# MCU.net
KiCad netlist of a schematic drawn in Altium Designer
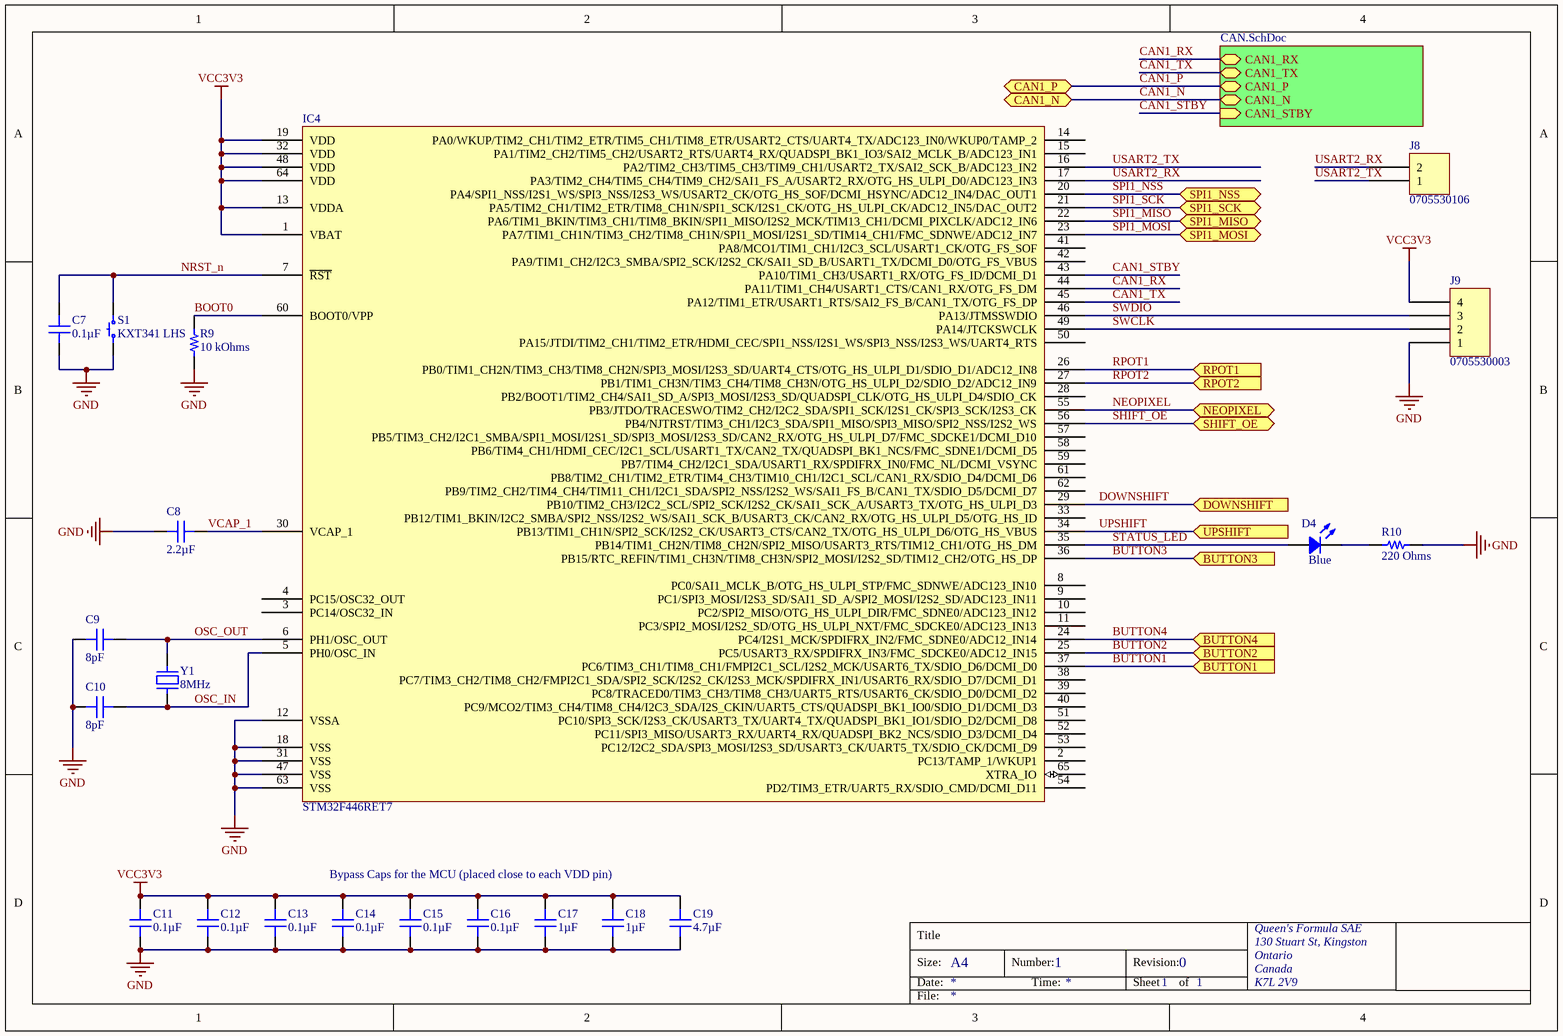
[diagram p0: MCU.SchDoc]

(export (version "E")
  (design (tool "Eeschema 10.0.6"))
  (components
    (comp (ref "C7")
      (value "0.1µF")
      (footprint "CAP 0402_1005")
      (description "CAP CER 0402 0.1UF 16V X7R 10%")
      (fields (field (name "PART NUMBER") "C0402C104K4RECAUTO") (field (name "MANUFACTURER") "KEMET"))
      (libsource (lib "CAL") (part "Capacitor"))
    )
    (comp (ref "C8")
      (value "2.2µF")
      (footprint "CAP 0402_1005")
      (description "CAP CER 2.2UF 16V X5R 0402")
      (fields
        (field (name "PART NUMBER") "CL05A225KO5NQNC")
        (field (name "MANUFACTURER") "Samsung Electro-Mechanics")
      )
      (libsource (lib "CAL") (part "Capacitor"))
    )
    (comp (ref "C9")
      (value "8pF")
      (footprint "CAP 0402_1005")
      (description "CAP CER 8PF 50V NP0 0402")
      (fields
        (field (name "PART NUMBER") "C1005NP01H080D050BA")
        (field (name "MANUFACTURER") "TDK Corporation")
      )
      (libsource (lib "Celestial") (part "Capacitor"))
    )
    (comp (ref "C10")
      (value "8pF")
      (footprint "CAP 0402_1005")
      (description "CAP CER 8PF 50V NP0 0402")
      (fields
        (field (name "PART NUMBER") "C1005NP01H080D050BA")
        (field (name "MANUFACTURER") "TDK Corporation")
      )
      (libsource (lib "Celestial") (part "Capacitor"))
    )
    (comp (ref "C11")
      (value "0.1µF")
      (footprint "CAP 0402_1005")
      (description "CAP CER 0402 0.1UF 16V X7R 10%")
      (fields (field (name "PART NUMBER") "C0402C104K4RECAUTO") (field (name "MANUFACTURER") "KEMET"))
      (libsource (lib "CAL") (part "Capacitor"))
    )
    (comp (ref "C12")
      (value "0.1µF")
      (footprint "CAP 0402_1005")
      (description "CAP CER 0402 0.1UF 16V X7R 10%")
      (fields (field (name "PART NUMBER") "C0402C104K4RECAUTO") (field (name "MANUFACTURER") "KEMET"))
      (libsource (lib "CAL") (part "Capacitor"))
    )
    (comp (ref "C13")
      (value "0.1µF")
      (footprint "CAP 0402_1005")
      (description "CAP CER 0402 0.1UF 16V X7R 10%")
      (fields (field (name "PART NUMBER") "C0402C104K4RECAUTO") (field (name "MANUFACTURER") "KEMET"))
      (libsource (lib "CAL") (part "Capacitor"))
    )
    (comp (ref "C14")
      (value "0.1µF")
      (footprint "CAP 0402_1005")
      (description "CAP CER 0402 0.1UF 16V X7R 10%")
      (fields (field (name "PART NUMBER") "C0402C104K4RECAUTO") (field (name "MANUFACTURER") "KEMET"))
      (libsource (lib "CAL") (part "Capacitor"))
    )
    (comp (ref "C15")
      (value "0.1µF")
      (footprint "CAP 0402_1005")
      (description "CAP CER 0402 0.1UF 16V X7R 10%")
      (fields (field (name "PART NUMBER") "C0402C104K4RECAUTO") (field (name "MANUFACTURER") "KEMET"))
      (libsource (lib "CAL") (part "Capacitor"))
    )
    (comp (ref "C16")
      (value "0.1µF")
      (footprint "CAP 0402_1005")
      (description "CAP CER 0402 0.1UF 16V X7R 10%")
      (fields (field (name "PART NUMBER") "C0402C104K4RECAUTO") (field (name "MANUFACTURER") "KEMET"))
      (libsource (lib "CAL") (part "Capacitor"))
    )
    (comp (ref "C17")
      (value "1µF")
      (footprint "CAP 0402_1005")
      (description "CAP CER 1UF 10V X5R 0402")
      (fields
        (field (name "PART NUMBER") "CGB2A1X5R1A105K033BC")
        (field (name "MANUFACTURER") "TDK Corporation")
      )
      (libsource (lib "CAL") (part "Capacitor"))
    )
    (comp (ref "C18")
      (value "1µF")
      (footprint "CAP 0402_1005")
      (description "CAP CER 1UF 10V X5R 0402")
      (fields
        (field (name "PART NUMBER") "CGB2A1X5R1A105K033BC")
        (field (name "MANUFACTURER") "TDK Corporation")
      )
      (libsource (lib "CAL") (part "Capacitor"))
    )
    (comp (ref "C19")
      (value "4.7µF")
      (footprint "CAP 0402_1005")
      (description "CAP CER 4.7UF 10V X5R 0402")
      (fields
        (field (name "PART NUMBER") "C1005X5R1A475K050BC")
        (field (name "MANUFACTURER") "TDK Corporation")
      )
      (libsource (lib "CAL") (part "Capacitor"))
    )
    (comp (ref "D4")
      (value "Blue")
      (footprint "LED 0402_1005 BLUE")
      (description "LED BLUE CLEAR CHIP SMD")
      (fields (field (name "PART NUMBER") "APHHS1005QBC/D") (field (name "MANUFACTURER") "Kingbright"))
      (libsource (lib "Celestial") (part "LED"))
    )
    (comp (ref "IC4")
      (value "STM32F446RET7")
      (footprint "ST LQFP-64 10X10MM")
      (description "IC MCU 32BIT 512KB FLASH 64LQFP")
      (fields (field (name "MANUFACTURER") "STMicroelectronics"))
      (libsource (lib "Celestial") (part "ST STM32F446 64PIN"))
    )
    (comp (ref "J8")
      (value "0705530106")
      (footprint "MOLEX SDA-70553-2PIN")
      (description "CONN HEADER R/A 2POS 2.54MM")
      (fields (field (name "MANUFACTURER") "Molex"))
      (libsource (lib "Celestial") (part "2 Pin"))
    )
    (comp (ref "J9")
      (value "0705530003")
      (footprint "MOLEX SDA-70553-4PIN")
      (description "CONN HEADER R/A 4POS 2.54MM")
      (fields (field (name "MANUFACTURER") "Molex"))
      (libsource (lib "Celestial") (part "4 Pin"))
    )
    (comp (ref "R9")
      (value "10 kOhms")
      (footprint "RES 0402_1005")
      (description "RES SMD 10K OHM 0.5% 1/16W 0402")
      (fields (field (name "PART NUMBER") "CRCW040210K0DHEDP") (field (name "MANUFACTURER") "Vishay Dale"))
      (libsource (lib "CAL") (part "Resistor"))
    )
    (comp (ref "R10")
      (value "220 Ohms")
      (footprint "RES 0402_1005")
      (description "CRGCQ 0402 220R 5%")
      (fields
        (field (name "PART NUMBER") "CRGCQ0402J220R")
        (field (name "MANUFACTURER") "TE Connectivity Passive Product")
      )
      (libsource (lib "CAL") (part "Resistor"))
    )
    (comp (ref "S1")
      (value "KXT341 LHS")
      (footprint "C&K KXT3")
      (description "SWITCH TACTILE SPST-NO 0.02A 15V")
      (fields (field (name "MANUFACTURER") "C&K"))
      (libsource (lib "Celestial") (part "SPST-NO 2 PIN"))
    )
    (comp (ref "Y1")
      (value "8MHz")
      (footprint "NDK NX3225GD")
      (description "CRYSTAL 8.0000MHZ 8PF SMD")
      (fields
        (field (name "PART NUMBER") "NX3225GD-8MHZ-STD-CRA-3")
        (field (name "MANUFACTURER") "NDK America, Inc.")
      )
      (libsource (lib "Celestial") (part "NDK NX3225GD"))
    )
  )
  (nets
    (net (code "1") (name "/BOOT0") (class "Default")
      (node (ref "IC4") (pin "60") (pinfunction "BOOT0/VPP_60") (pintype "passive"))
      (node (ref "R9") (pin "2") (pinfunction "2_2") (pintype "passive"))
    )
    (net (code "2") (name "/BUTTON1") (class "Default")
      (node (ref "IC4") (pin "37") (pinfunction "PC6/TIM3_CH1/TIM8_CH1/FMPI2C1_SCL/I2S2_MCK/USART6_TX/SDIO_D6/DCMI_D0_37") (pintype "passive"))
    )
    (net (code "3") (name "/BUTTON2") (class "Default")
      (node (ref "IC4") (pin "25") (pinfunction "PC5/USART3_RX/SPDIFRX_IN3/FMC_SDCKE0/ADC12_IN15_25") (pintype "passive"))
    )
    (net (code "4") (name "/BUTTON3") (class "Default")
      (node (ref "IC4") (pin "36") (pinfunction "PB15/RTC_REFIN/TIM1_CH3N/TIM8_CH3N/SPI2_MOSI/I2S2_SD/TIM12_CH2/OTG_HS_DP_36") (pintype "passive"))
    )
    (net (code "5") (name "/BUTTON4") (class "Default")
      (node (ref "IC4") (pin "24") (pinfunction "PC4/I2S1_MCK/SPDIFRX_IN2/FMC_SDNE0/ADC12_IN14_24") (pintype "passive"))
    )
    (net (code "8") (name "/CAN1_RX") (class "Default")
      (node (ref "IC4") (pin "44") (pinfunction "PA11/TIM1_CH4/USART1_CTS/CAN1_RX/OTG_FS_DM_44") (pintype "passive"))
    )
    (net (code "9") (name "/CAN1_STBY") (class "Default")
      (node (ref "IC4") (pin "43") (pinfunction "PA10/TIM1_CH3/USART1_RX/OTG_FS_ID/DCMI_D1_43") (pintype "passive"))
    )
    (net (code "10") (name "/CAN1_TX") (class "Default")
      (node (ref "IC4") (pin "45") (pinfunction "PA12/TIM1_ETR/USART1_RTS/SAI2_FS_B/CAN1_TX/OTG_FS_DP_45") (pintype "passive"))
    )
    (net (code "11") (name "/DOWNSHIFT") (class "Default")
      (node (ref "IC4") (pin "29") (pinfunction "PB10/TIM2_CH3/I2C2_SCL/SPI2_SCK/I2S2_CK/SAI1_SCK_A/USART3_TX/OTG_HS_ULPI_D3_29") (pintype "passive"))
    )
    (net (code "12") (name "/NEOPIXEL") (class "Default")
      (node (ref "IC4") (pin "55") (pinfunction "PB3/JTDO/TRACESWO/TIM2_CH2/I2C2_SDA/SPI1_SCK/I2S1_CK/SPI3_SCK/I2S3_CK_55") (pintype "passive"))
    )
    (net (code "13") (name "/NRST_n") (class "Default")
      (node (ref "C7") (pin "2") (pinfunction "2_2") (pintype "passive"))
      (node (ref "IC4") (pin "7") (pinfunction "~{RST}_7") (pintype "passive"))
      (node (ref "S1") (pin "2") (pinfunction "2_2") (pintype "passive"))
    )
    (net (code "14") (name "/OSC_IN") (class "Default")
      (node (ref "C10") (pin "2") (pinfunction "2_2") (pintype "passive"))
      (node (ref "IC4") (pin "5") (pinfunction "PH0/OSC_IN_5") (pintype "passive"))
      (node (ref "Y1") (pin "1") (pinfunction "1_1") (pintype "passive"))
    )
    (net (code "15") (name "/OSC_OUT") (class "Default")
      (node (ref "C9") (pin "2") (pinfunction "2_2") (pintype "passive"))
      (node (ref "IC4") (pin "6") (pinfunction "PH1/OSC_OUT_6") (pintype "passive"))
      (node (ref "Y1") (pin "2") (pinfunction "2_2") (pintype "passive"))
    )
    (net (code "16") (name "/RPOT1") (class "Default")
      (node (ref "IC4") (pin "26") (pinfunction "PB0/TIM1_CH2N/TIM3_CH3/TIM8_CH2N/SPI3_MOSI/I2S3_SD/UART4_CTS/OTG_HS_ULPI_D1/SDIO_D1/ADC12_IN8_26") (pintype "passive"))
    )
    (net (code "17") (name "/RPOT2") (class "Default")
      (node (ref "IC4") (pin "27") (pinfunction "PB1/TIM1_CH3N/TIM3_CH4/TIM8_CH3N/OTG_HS_ULPI_D2/SDIO_D2/ADC12_IN9_27") (pintype "passive"))
    )
    (net (code "18") (name "/SHIFT_OE") (class "Default")
      (node (ref "IC4") (pin "56") (pinfunction "PB4/NJTRST/TIM3_CH1/I2C3_SDA/SPI1_MISO/SPI3_MISO/SPI2_NSS/I2S2_WS_56") (pintype "passive"))
    )
    (net (code "19") (name "/SPI1_MISO") (class "Default")
      (node (ref "IC4") (pin "22") (pinfunction "PA6/TIM1_BKIN/TIM3_CH1/TIM8_BKIN/SPI1_MISO/I2S2_MCK/TIM13_CH1/DCMI_PIXCLK/ADC12_IN6_22") (pintype "passive"))
    )
    (net (code "20") (name "/SPI1_MOSI") (class "Default")
      (node (ref "IC4") (pin "23") (pinfunction "PA7/TIM1_CH1N/TIM3_CH2/TIM8_CH1N/SPI1_MOSI/I2S1_SD/TIM14_CH1/FMC_SDNWE/ADC12_IN7_23") (pintype "passive"))
    )
    (net (code "21") (name "/SPI1_NSS") (class "Default")
      (node (ref "IC4") (pin "20") (pinfunction "PA4/SPI1_NSS/I2S1_WS/SPI3_NSS/I2S3_WS/USART2_CK/OTG_HS_SOF/DCMI_HSYNC/ADC12_IN4/DAC_OUT1_20") (pintype "passive"))
    )
    (net (code "22") (name "/SPI1_SCK") (class "Default")
      (node (ref "IC4") (pin "21") (pinfunction "PA5/TIM2_CH1/TIM2_ETR/TIM8_CH1N/SPI1_SCK/I2S1_CK/OTG_HS_ULPI_CK/ADC12_IN5/DAC_OUT2_21") (pintype "passive"))
    )
    (net (code "23") (name "/STATUS_LED") (class "Default")
      (node (ref "D4") (pin "1") (pinfunction "1_1") (pintype "passive"))
      (node (ref "IC4") (pin "35") (pinfunction "PB14/TIM1_CH2N/TIM8_CH2N/SPI2_MISO/USART3_RTS/TIM12_CH1/OTG_HS_DM_35") (pintype "passive"))
    )
    (net (code "24") (name "/SWCLK") (class "Default")
      (node (ref "IC4") (pin "49") (pinfunction "PA14/JTCKSWCLK_49") (pintype "passive"))
      (node (ref "J9") (pin "2") (pinfunction "2_2") (pintype "passive"))
    )
    (net (code "25") (name "/SWDIO") (class "Default")
      (node (ref "IC4") (pin "46") (pinfunction "PA13/JTMSSWDIO_46") (pintype "passive"))
      (node (ref "J9") (pin "3") (pinfunction "3_3") (pintype "passive"))
    )
    (net (code "26") (name "/UPSHIFT") (class "Default")
      (node (ref "IC4") (pin "34") (pinfunction "PB13/TIM1_CH1N/SPI2_SCK/I2S2_CK/USART3_CTS/CAN2_TX/OTG_HS_ULPI_D6/OTG_HS_VBUS_34") (pintype "passive"))
    )
    (net (code "27") (name "/USART2_RX") (class "Default")
      (node (ref "IC4") (pin "17") (pinfunction "PA3/TIM2_CH4/TIM5_CH4/TIM9_CH2/SAI1_FS_A/USART2_RX/OTG_HS_ULPI_D0/ADC123_IN3_17") (pintype "passive"))
      (node (ref "J8") (pin "2") (pinfunction "2_2") (pintype "passive"))
    )
    (net (code "28") (name "/USART2_TX") (class "Default")
      (node (ref "IC4") (pin "16") (pinfunction "PA2/TIM2_CH3/TIM5_CH3/TIM9_CH1/USART2_TX/SAI2_SCK_B/ADC123_IN2_16") (pintype "passive"))
      (node (ref "J8") (pin "1") (pinfunction "1_1") (pintype "passive"))
    )
    (net (code "29") (name "/VCAP_1") (class "Default")
      (node (ref "C8") (pin "1") (pinfunction "1_1") (pintype "passive"))
      (node (ref "IC4") (pin "30") (pinfunction "VCAP_1_30") (pintype "passive"))
    )
    (net (code "30") (name "GND") (class "Default")
      (node (ref "C10") (pin "1") (pinfunction "1_1") (pintype "passive"))
      (node (ref "C11") (pin "1") (pinfunction "1_1") (pintype "passive"))
      (node (ref "C12") (pin "1") (pinfunction "1_1") (pintype "passive"))
      (node (ref "C13") (pin "1") (pinfunction "1_1") (pintype "passive"))
      (node (ref "C14") (pin "1") (pinfunction "1_1") (pintype "passive"))
      (node (ref "C15") (pin "1") (pinfunction "1_1") (pintype "passive"))
      (node (ref "C16") (pin "1") (pinfunction "1_1") (pintype "passive"))
      (node (ref "C17") (pin "1") (pinfunction "1_1") (pintype "passive"))
      (node (ref "C18") (pin "1") (pinfunction "1_1") (pintype "passive"))
      (node (ref "C19") (pin "1") (pinfunction "1_1") (pintype "passive"))
      (node (ref "C7") (pin "1") (pinfunction "1_1") (pintype "passive"))
      (node (ref "C8") (pin "2") (pinfunction "2_2") (pintype "passive"))
      (node (ref "C9") (pin "1") (pinfunction "1_1") (pintype "passive"))
      (node (ref "IC4") (pin "12") (pinfunction "VSSA_12") (pintype "passive"))
      (node (ref "IC4") (pin "18") (pinfunction "VSS_18") (pintype "passive"))
      (node (ref "IC4") (pin "31") (pinfunction "VSS_31") (pintype "passive"))
      (node (ref "IC4") (pin "47") (pinfunction "VSS_47") (pintype "passive"))
      (node (ref "IC4") (pin "63") (pinfunction "VSS_63") (pintype "passive"))
      (node (ref "J9") (pin "1") (pinfunction "1_1") (pintype "passive"))
      (node (ref "R10") (pin "2") (pinfunction "2_2") (pintype "passive"))
      (node (ref "R9") (pin "1") (pinfunction "1_1") (pintype "passive"))
      (node (ref "S1") (pin "1") (pinfunction "1_1") (pintype "passive"))
    )
    (net (code "31") (name "Net-(D4-Pad2)") (class "Default")
      (node (ref "D4") (pin "2") (pinfunction "2_2") (pintype "passive"))
      (node (ref "R10") (pin "1") (pinfunction "1_1") (pintype "passive"))
    )
    (net (code "32") (name "VCC3V3") (class "Default")
      (node (ref "C11") (pin "2") (pinfunction "2_2") (pintype "passive"))
      (node (ref "C12") (pin "2") (pinfunction "2_2") (pintype "passive"))
      (node (ref "C13") (pin "2") (pinfunction "2_2") (pintype "passive"))
      (node (ref "C14") (pin "2") (pinfunction "2_2") (pintype "passive"))
      (node (ref "C15") (pin "2") (pinfunction "2_2") (pintype "passive"))
      (node (ref "C16") (pin "2") (pinfunction "2_2") (pintype "passive"))
      (node (ref "C17") (pin "2") (pinfunction "2_2") (pintype "passive"))
      (node (ref "C18") (pin "2") (pinfunction "2_2") (pintype "passive"))
      (node (ref "C19") (pin "2") (pinfunction "2_2") (pintype "passive"))
      (node (ref "IC4") (pin "1") (pinfunction "VBAT_1") (pintype "passive"))
      (node (ref "IC4") (pin "13") (pinfunction "VDDA_13") (pintype "passive"))
      (node (ref "IC4") (pin "19") (pinfunction "VDD_19") (pintype "passive"))
      (node (ref "IC4") (pin "32") (pinfunction "VDD_32") (pintype "passive"))
      (node (ref "IC4") (pin "48") (pinfunction "VDD_48") (pintype "passive"))
      (node (ref "IC4") (pin "64") (pinfunction "VDD_64") (pintype "passive"))
      (node (ref "J9") (pin "4") (pinfunction "4_4") (pintype "passive"))
    )
    (net (code "33") (name "unconnected-(IC4-PA0{slash}WKUP{slash}TIM2_CH1{slash}TIM2_ETR{slash}TIM5_CH1{slash}TIM8_ETR{slash}USART2_CTS{slash}UART4_TX{slash}ADC123_IN0{slash}WKUP0{slash}TAMP_2-Pad14)") (class "Default")
      (node (ref "IC4") (pin "14") (pinfunction "PA0/WKUP/TIM2_CH1/TIM2_ETR/TIM5_CH1/TIM8_ETR/USART2_CTS/UART4_TX/ADC123_IN0/WKUP0/TAMP_2_14") (pintype "passive"))
    )
    (net (code "34") (name "unconnected-(IC4-PA1{slash}TIM2_CH2{slash}TIM5_CH2{slash}USART2_RTS{slash}UART4_RX{slash}QUADSPI_BK1_IO3{slash}SAI2_MCLK_B{slash}ADC123_IN1-Pad15)") (class "Default")
      (node (ref "IC4") (pin "15") (pinfunction "PA1/TIM2_CH2/TIM5_CH2/USART2_RTS/UART4_RX/QUADSPI_BK1_IO3/SAI2_MCLK_B/ADC123_IN1_15") (pintype "passive"))
    )
    (net (code "35") (name "unconnected-(IC4-PA8{slash}MCO1{slash}TIM1_CH1{slash}I2C3_SCL{slash}USART1_CK{slash}OTG_FS_SOF-Pad41)") (class "Default")
      (node (ref "IC4") (pin "41") (pinfunction "PA8/MCO1/TIM1_CH1/I2C3_SCL/USART1_CK/OTG_FS_SOF_41") (pintype "passive"))
    )
    (net (code "36") (name "unconnected-(IC4-PA9{slash}TIM1_CH2{slash}I2C3_SMBA{slash}SPI2_SCK{slash}I2S2_CK{slash}SAI1_SD_B{slash}USART1_TX{slash}DCMI_D0{slash}OTG_FS_VBUS-Pad42)") (class "Default")
      (node (ref "IC4") (pin "42") (pinfunction "PA9/TIM1_CH2/I2C3_SMBA/SPI2_SCK/I2S2_CK/SAI1_SD_B/USART1_TX/DCMI_D0/OTG_FS_VBUS_42") (pintype "passive"))
    )
    (net (code "37") (name "unconnected-(IC4-PA15{slash}JTDI{slash}TIM2_CH1{slash}TIM2_ETR{slash}HDMI_CEC{slash}SPI1_NSS{slash}I2S1_WS{slash}SPI3_NSS{slash}I2S3_WS{slash}UART4_RTS-Pad50)") (class "Default")
      (node (ref "IC4") (pin "50") (pinfunction "PA15/JTDI/TIM2_CH1/TIM2_ETR/HDMI_CEC/SPI1_NSS/I2S1_WS/SPI3_NSS/I2S3_WS/UART4_RTS_50") (pintype "passive"))
    )
    (net (code "38") (name "unconnected-(IC4-PB2{slash}BOOT1{slash}TIM2_CH4{slash}SAI1_SD_A{slash}SPI3_MOSI{slash}I2S3_SD{slash}QUADSPI_CLK{slash}OTG_HS_ULPI_D4{slash}SDIO_CK-Pad28)") (class "Default")
      (node (ref "IC4") (pin "28") (pinfunction "PB2/BOOT1/TIM2_CH4/SAI1_SD_A/SPI3_MOSI/I2S3_SD/QUADSPI_CLK/OTG_HS_ULPI_D4/SDIO_CK_28") (pintype "passive"))
    )
    (net (code "39") (name "unconnected-(IC4-PB5{slash}TIM3_CH2{slash}I2C1_SMBA{slash}SPI1_MOSI{slash}I2S1_SD{slash}SPI3_MOSI{slash}I2S3_SD{slash}CAN2_RX{slash}OTG_HS_ULPI_D7{slash}FMC_SDCKE1{slash}DCMI_D10-Pad57)") (class "Default")
      (node (ref "IC4") (pin "57") (pinfunction "PB5/TIM3_CH2/I2C1_SMBA/SPI1_MOSI/I2S1_SD/SPI3_MOSI/I2S3_SD/CAN2_RX/OTG_HS_ULPI_D7/FMC_SDCKE1/DCMI_D10_57") (pintype "passive"))
    )
    (net (code "40") (name "unconnected-(IC4-PB6{slash}TIM4_CH1{slash}HDMI_CEC{slash}I2C1_SCL{slash}USART1_TX{slash}CAN2_TX{slash}QUADSPI_BK1_NCS{slash}FMC_SDNE1{slash}DCMI_D5-Pad58)") (class "Default")
      (node (ref "IC4") (pin "58") (pinfunction "PB6/TIM4_CH1/HDMI_CEC/I2C1_SCL/USART1_TX/CAN2_TX/QUADSPI_BK1_NCS/FMC_SDNE1/DCMI_D5_58") (pintype "passive"))
    )
    (net (code "41") (name "unconnected-(IC4-PB7{slash}TIM4_CH2{slash}I2C1_SDA{slash}USART1_RX{slash}SPDIFRX_IN0{slash}FMC_NL{slash}DCMI_VSYNC-Pad59)") (class "Default")
      (node (ref "IC4") (pin "59") (pinfunction "PB7/TIM4_CH2/I2C1_SDA/USART1_RX/SPDIFRX_IN0/FMC_NL/DCMI_VSYNC_59") (pintype "passive"))
    )
    (net (code "42") (name "unconnected-(IC4-PB8{slash}TIM2_CH1{slash}TIM2_ETR{slash}TIM4_CH3{slash}TIM10_CH1{slash}I2C1_SCL{slash}CAN1_RX{slash}SDIO_D4{slash}DCMI_D6-Pad61)") (class "Default")
      (node (ref "IC4") (pin "61") (pinfunction "PB8/TIM2_CH1/TIM2_ETR/TIM4_CH3/TIM10_CH1/I2C1_SCL/CAN1_RX/SDIO_D4/DCMI_D6_61") (pintype "passive"))
    )
    (net (code "43") (name "unconnected-(IC4-PB9{slash}TIM2_CH2{slash}TIM4_CH4{slash}TIM11_CH1{slash}I2C1_SDA{slash}SPI2_NSS{slash}I2S2_WS{slash}SAI1_FS_B{slash}CAN1_TX{slash}SDIO_D5{slash}DCMI_D7-Pad62)") (class "Default")
      (node (ref "IC4") (pin "62") (pinfunction "PB9/TIM2_CH2/TIM4_CH4/TIM11_CH1/I2C1_SDA/SPI2_NSS/I2S2_WS/SAI1_FS_B/CAN1_TX/SDIO_D5/DCMI_D7_62") (pintype "passive"))
    )
    (net (code "44") (name "unconnected-(IC4-PB12{slash}TIM1_BKIN{slash}I2C2_SMBA{slash}SPI2_NSS{slash}I2S2_WS{slash}SAI1_SCK_B{slash}USART3_CK{slash}CAN2_RX{slash}OTG_HS_ULPI_D5{slash}OTG_HS_ID-Pad33)") (class "Default")
      (node (ref "IC4") (pin "33") (pinfunction "PB12/TIM1_BKIN/I2C2_SMBA/SPI2_NSS/I2S2_WS/SAI1_SCK_B/USART3_CK/CAN2_RX/OTG_HS_ULPI_D5/OTG_HS_ID_33") (pintype "passive"))
    )
    (net (code "45") (name "unconnected-(IC4-PC0{slash}SAI1_MCLK_B{slash}OTG_HS_ULPI_STP{slash}FMC_SDNWE{slash}ADC123_IN10-Pad8)") (class "Default")
      (node (ref "IC4") (pin "8") (pinfunction "PC0/SAI1_MCLK_B/OTG_HS_ULPI_STP/FMC_SDNWE/ADC123_IN10_8") (pintype "passive"))
    )
    (net (code "46") (name "unconnected-(IC4-PC1{slash}SPI3_MOSI{slash}I2S3_SD{slash}SAI1_SD_A{slash}SPI2_MOSI{slash}I2S2_SD{slash}ADC123_IN11-Pad9)") (class "Default")
      (node (ref "IC4") (pin "9") (pinfunction "PC1/SPI3_MOSI/I2S3_SD/SAI1_SD_A/SPI2_MOSI/I2S2_SD/ADC123_IN11_9") (pintype "passive"))
    )
    (net (code "47") (name "unconnected-(IC4-PC2{slash}SPI2_MISO{slash}OTG_HS_ULPI_DIR{slash}FMC_SDNE0{slash}ADC123_IN12-Pad10)") (class "Default")
      (node (ref "IC4") (pin "10") (pinfunction "PC2/SPI2_MISO/OTG_HS_ULPI_DIR/FMC_SDNE0/ADC123_IN12_10") (pintype "passive"))
    )
    (net (code "48") (name "unconnected-(IC4-PC3{slash}SPI2_MOSI{slash}I2S2_SD{slash}OTG_HS_ULPI_NXT{slash}FMC_SDCKE0{slash}ADC123_IN13-Pad11)") (class "Default")
      (node (ref "IC4") (pin "11") (pinfunction "PC3/SPI2_MOSI/I2S2_SD/OTG_HS_ULPI_NXT/FMC_SDCKE0/ADC123_IN13_11") (pintype "passive"))
    )
    (net (code "49") (name "unconnected-(IC4-PC7{slash}TIM3_CH2{slash}TIM8_CH2{slash}FMPI2C1_SDA{slash}SPI2_SCK{slash}I2S2_CK{slash}I2S3_MCK{slash}SPDIFRX_IN1{slash}USART6_RX{slash}SDIO_D7{slash}DCMI_D1-Pad38)") (class "Default")
      (node (ref "IC4") (pin "38") (pinfunction "PC7/TIM3_CH2/TIM8_CH2/FMPI2C1_SDA/SPI2_SCK/I2S2_CK/I2S3_MCK/SPDIFRX_IN1/USART6_RX/SDIO_D7/DCMI_D1_38") (pintype "passive"))
    )
    (net (code "50") (name "unconnected-(IC4-PC8{slash}TRACED0{slash}TIM3_CH3{slash}TIM8_CH3{slash}UART5_RTS{slash}USART6_CK{slash}SDIO_D0{slash}DCMI_D2-Pad39)") (class "Default")
      (node (ref "IC4") (pin "39") (pinfunction "PC8/TRACED0/TIM3_CH3/TIM8_CH3/UART5_RTS/USART6_CK/SDIO_D0/DCMI_D2_39") (pintype "passive"))
    )
    (net (code "51") (name "unconnected-(IC4-PC9{slash}MCO2{slash}TIM3_CH4{slash}TIM8_CH4{slash}I2C3_SDA{slash}I2S_CKIN{slash}UART5_CTS{slash}QUADSPI_BK1_IO0{slash}SDIO_D1{slash}DCMI_D3-Pad40)") (class "Default")
      (node (ref "IC4") (pin "40") (pinfunction "PC9/MCO2/TIM3_CH4/TIM8_CH4/I2C3_SDA/I2S_CKIN/UART5_CTS/QUADSPI_BK1_IO0/SDIO_D1/DCMI_D3_40") (pintype "passive"))
    )
    (net (code "52") (name "unconnected-(IC4-PC10{slash}SPI3_SCK{slash}I2S3_CK{slash}USART3_TX{slash}UART4_TX{slash}QUADSPI_BK1_IO1{slash}SDIO_D2{slash}DCMI_D8-Pad51)") (class "Default")
      (node (ref "IC4") (pin "51") (pinfunction "PC10/SPI3_SCK/I2S3_CK/USART3_TX/UART4_TX/QUADSPI_BK1_IO1/SDIO_D2/DCMI_D8_51") (pintype "passive"))
    )
    (net (code "53") (name "unconnected-(IC4-PC11{slash}SPI3_MISO{slash}USART3_RX{slash}UART4_RX{slash}QUADSPI_BK2_NCS{slash}SDIO_D3{slash}DCMI_D4-Pad52)") (class "Default")
      (node (ref "IC4") (pin "52") (pinfunction "PC11/SPI3_MISO/USART3_RX/UART4_RX/QUADSPI_BK2_NCS/SDIO_D3/DCMI_D4_52") (pintype "passive"))
    )
    (net (code "54") (name "unconnected-(IC4-PC12{slash}I2C2_SDA{slash}SPI3_MOSI{slash}I2S3_SD{slash}USART3_CK{slash}UART5_TX{slash}SDIO_CK{slash}DCMI_D9-Pad53)") (class "Default")
      (node (ref "IC4") (pin "53") (pinfunction "PC12/I2C2_SDA/SPI3_MOSI/I2S3_SD/USART3_CK/UART5_TX/SDIO_CK/DCMI_D9_53") (pintype "passive"))
    )
    (net (code "55") (name "unconnected-(IC4-PC13{slash}TAMP_1{slash}WKUP1-Pad2)") (class "Default")
      (node (ref "IC4") (pin "2") (pinfunction "PC13/TAMP_1/WKUP1_2") (pintype "passive"))
    )
    (net (code "56") (name "unconnected-(IC4-PC14{slash}OSC32_IN-Pad3)") (class "Default")
      (node (ref "IC4") (pin "3") (pinfunction "PC14/OSC32_IN_3") (pintype "passive"))
    )
    (net (code "57") (name "unconnected-(IC4-PC15{slash}OSC32_OUT-Pad4)") (class "Default")
      (node (ref "IC4") (pin "4") (pinfunction "PC15/OSC32_OUT_4") (pintype "passive"))
    )
    (net (code "58") (name "unconnected-(IC4-PD2{slash}TIM3_ETR{slash}UART5_RX{slash}SDIO_CMD{slash}DCMI_D11-Pad54)") (class "Default")
      (node (ref "IC4") (pin "54") (pinfunction "PD2/TIM3_ETR/UART5_RX/SDIO_CMD/DCMI_D11_54") (pintype "passive"))
    )
    (net (code "59") (name "unconnected-(IC4-XTRA_IO-Pad65)") (class "Default")
      (node (ref "IC4") (pin "65") (pinfunction "XTRA_IO_65") (pintype "bidirectional"))
    )
  )
)
